# Breakout_ER-TFT1_28-2.net
KiCad netlist of a schematic drawn in Altium Designer
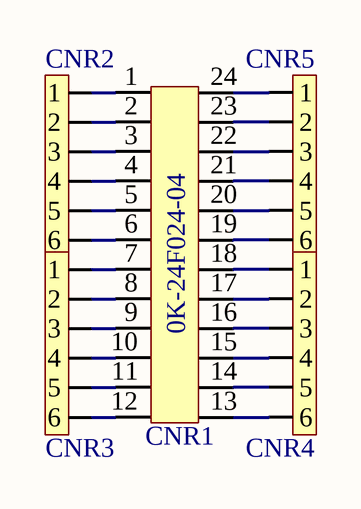
[diagram p0: Breakout_ER-TFT1.28-2.SchDoc]

(export (version "E")
  (design (tool "Eeschema 10.0.6"))
  (components
    (comp (ref "CNR1")
      (value "0K-24F024-04")
      (footprint "0K-24F024-04")
      (description "24 Pins 0.4mm Pitch ZIF Connector")
      (libsource (lib "Open-Wearable") (part "{gt}CNR{colon}IDC-2x12"))
    )
    (comp (ref "CNR2")
      (value "- CNR-IDC:6x1")
      (footprint "SIP06-2.54P")
      (libsource (lib "Open-Wearable") (part "- CNR-IDC{colon}6x1"))
    )
    (comp (ref "CNR3")
      (value "~")
      (footprint "SIP06-2.54P")
      (libsource (lib "") (part "- CNR-IDC{colon}6x1_1"))
    )
    (comp (ref "CNR4")
      (value "~")
      (footprint "SIP06-2.54P")
      (libsource (lib "*") (part "- CNR-IDC{colon}6x1"))
    )
    (comp (ref "CNR5")
      (value "~")
      (footprint "SIP06-2.54P")
      (libsource (lib "*") (part "- CNR-IDC{colon}6x1"))
    )
  )
  (nets
    (net (code "1") (name "Net-(CNR1-Pad1)") (class "Default")
      (node (ref "CNR1") (pin "1") (pinfunction "1_1") (pintype "passive"))
      (node (ref "CNR2") (pin "1") (pinfunction "1_1") (pintype "passive"))
    )
    (net (code "2") (name "Net-(CNR1-Pad2)") (class "Default")
      (node (ref "CNR1") (pin "2") (pinfunction "2_2") (pintype "passive"))
      (node (ref "CNR2") (pin "2") (pinfunction "2_2") (pintype "passive"))
    )
    (net (code "3") (name "Net-(CNR1-Pad3)") (class "Default")
      (node (ref "CNR1") (pin "3") (pinfunction "3_3") (pintype "passive"))
      (node (ref "CNR2") (pin "3") (pinfunction "3_3") (pintype "passive"))
    )
    (net (code "4") (name "Net-(CNR1-Pad4)") (class "Default")
      (node (ref "CNR1") (pin "4") (pinfunction "4_4") (pintype "passive"))
      (node (ref "CNR2") (pin "4") (pinfunction "4_4") (pintype "passive"))
    )
    (net (code "5") (name "Net-(CNR1-Pad5)") (class "Default")
      (node (ref "CNR1") (pin "5") (pinfunction "5_5") (pintype "passive"))
      (node (ref "CNR2") (pin "5") (pinfunction "5_5") (pintype "passive"))
    )
    (net (code "6") (name "Net-(CNR1-Pad6)") (class "Default")
      (node (ref "CNR1") (pin "6") (pinfunction "6_6") (pintype "passive"))
      (node (ref "CNR2") (pin "6") (pinfunction "6_6") (pintype "passive"))
    )
    (net (code "7") (name "Net-(CNR1-Pad7)") (class "Default")
      (node (ref "CNR1") (pin "7") (pinfunction "7_7") (pintype "passive"))
      (node (ref "CNR3") (pin "1") (pinfunction "1_1") (pintype "passive"))
    )
    (net (code "8") (name "Net-(CNR1-Pad8)") (class "Default")
      (node (ref "CNR1") (pin "8") (pinfunction "8_8") (pintype "passive"))
      (node (ref "CNR3") (pin "2") (pinfunction "2_2") (pintype "passive"))
    )
    (net (code "9") (name "Net-(CNR1-Pad9)") (class "Default")
      (node (ref "CNR1") (pin "9") (pinfunction "9_9") (pintype "passive"))
      (node (ref "CNR3") (pin "3") (pinfunction "3_3") (pintype "passive"))
    )
    (net (code "10") (name "Net-(CNR1-Pad10)") (class "Default")
      (node (ref "CNR1") (pin "10") (pinfunction "10_10") (pintype "passive"))
      (node (ref "CNR3") (pin "4") (pinfunction "4_4") (pintype "passive"))
    )
    (net (code "11") (name "Net-(CNR1-Pad11)") (class "Default")
      (node (ref "CNR1") (pin "11") (pinfunction "11_11") (pintype "passive"))
      (node (ref "CNR3") (pin "5") (pinfunction "5_5") (pintype "passive"))
    )
    (net (code "12") (name "Net-(CNR1-Pad12)") (class "Default")
      (node (ref "CNR1") (pin "12") (pinfunction "12_12") (pintype "passive"))
      (node (ref "CNR3") (pin "6") (pinfunction "6_6") (pintype "passive"))
    )
    (net (code "13") (name "Net-(CNR1-Pad13)") (class "Default")
      (node (ref "CNR1") (pin "13") (pinfunction "13_13") (pintype "passive"))
      (node (ref "CNR4") (pin "6") (pinfunction "6_6") (pintype "passive"))
    )
    (net (code "14") (name "Net-(CNR1-Pad14)") (class "Default")
      (node (ref "CNR1") (pin "14") (pinfunction "14_14") (pintype "passive"))
      (node (ref "CNR4") (pin "5") (pinfunction "5_5") (pintype "passive"))
    )
    (net (code "15") (name "Net-(CNR1-Pad15)") (class "Default")
      (node (ref "CNR1") (pin "15") (pinfunction "15_15") (pintype "passive"))
      (node (ref "CNR4") (pin "4") (pinfunction "4_4") (pintype "passive"))
    )
    (net (code "16") (name "Net-(CNR1-Pad16)") (class "Default")
      (node (ref "CNR1") (pin "16") (pinfunction "16_16") (pintype "passive"))
      (node (ref "CNR4") (pin "3") (pinfunction "3_3") (pintype "passive"))
    )
    (net (code "17") (name "Net-(CNR1-Pad17)") (class "Default")
      (node (ref "CNR1") (pin "17") (pinfunction "17_17") (pintype "passive"))
      (node (ref "CNR4") (pin "2") (pinfunction "2_2") (pintype "passive"))
    )
    (net (code "18") (name "Net-(CNR1-Pad18)") (class "Default")
      (node (ref "CNR1") (pin "18") (pinfunction "18_18") (pintype "passive"))
      (node (ref "CNR4") (pin "1") (pinfunction "1_1") (pintype "passive"))
    )
    (net (code "19") (name "Net-(CNR1-Pad19)") (class "Default")
      (node (ref "CNR1") (pin "19") (pinfunction "19_19") (pintype "passive"))
      (node (ref "CNR5") (pin "6") (pinfunction "6_6") (pintype "passive"))
    )
    (net (code "20") (name "Net-(CNR1-Pad20)") (class "Default")
      (node (ref "CNR1") (pin "20") (pinfunction "20_20") (pintype "passive"))
      (node (ref "CNR5") (pin "5") (pinfunction "5_5") (pintype "passive"))
    )
    (net (code "21") (name "Net-(CNR1-Pad21)") (class "Default")
      (node (ref "CNR1") (pin "21") (pinfunction "21_21") (pintype "passive"))
      (node (ref "CNR5") (pin "4") (pinfunction "4_4") (pintype "passive"))
    )
    (net (code "22") (name "Net-(CNR1-Pad22)") (class "Default")
      (node (ref "CNR1") (pin "22") (pinfunction "22_22") (pintype "passive"))
      (node (ref "CNR5") (pin "3") (pinfunction "3_3") (pintype "passive"))
    )
    (net (code "23") (name "Net-(CNR1-Pad23)") (class "Default")
      (node (ref "CNR1") (pin "23") (pinfunction "23_23") (pintype "passive"))
      (node (ref "CNR5") (pin "2") (pinfunction "2_2") (pintype "passive"))
    )
    (net (code "24") (name "Net-(CNR1-Pad24)") (class "Default")
      (node (ref "CNR1") (pin "24") (pinfunction "24_24") (pintype "passive"))
      (node (ref "CNR5") (pin "1") (pinfunction "1_1") (pintype "passive"))
    )
  )
)
